# Analog_out.net
KiCad netlist of a schematic drawn in Altium Designer
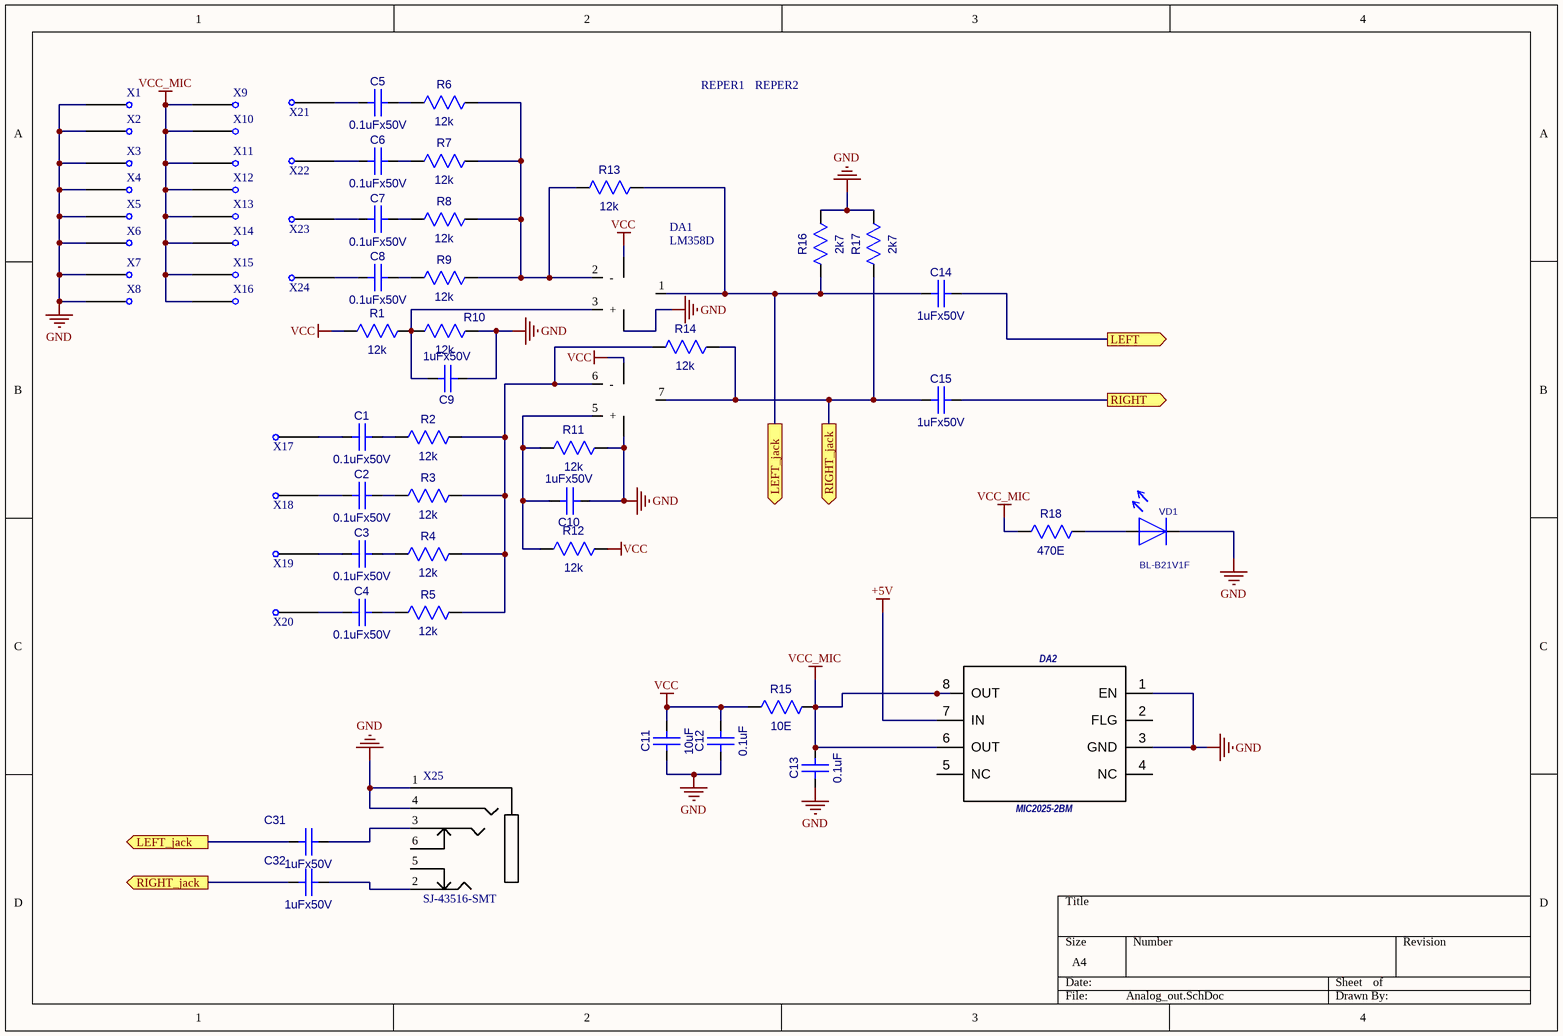
[diagram p0: Analog_out.SchDoc]

(export (version "E")
  (design (tool "Eeschema 10.0.6"))
  (components
    (comp (ref "C1")
      (value "0.1uFx50V")
      (footprint "CC0603-3M")
      (description "CC0603 X7R")
      (libsource (lib "gprs_modem") (part "CC0603"))
    )
    (comp (ref "C2")
      (value "0.1uFx50V")
      (footprint "CC0603-3M")
      (description "CC0603 X7R")
      (libsource (lib "gprs_modem") (part "CC0603"))
    )
    (comp (ref "C3")
      (value "0.1uFx50V")
      (footprint "CC0603-3M")
      (description "CC0603 X7R")
      (libsource (lib "gprs_modem") (part "CC0603"))
    )
    (comp (ref "C4")
      (value "0.1uFx50V")
      (footprint "CC0603-3M")
      (description "CC0603 X7R")
      (libsource (lib "gprs_modem") (part "CC0603"))
    )
    (comp (ref "C5")
      (value "0.1uFx50V")
      (footprint "CC0603-3M")
      (description "CC0603 X7R")
      (libsource (lib "gprs_modem") (part "CC0603"))
    )
    (comp (ref "C6")
      (value "0.1uFx50V")
      (footprint "CC0603-3M")
      (description "CC0603 X7R")
      (libsource (lib "gprs_modem") (part "CC0603"))
    )
    (comp (ref "C7")
      (value "0.1uFx50V")
      (footprint "CC0603-3M")
      (description "CC0603 X7R")
      (libsource (lib "gprs_modem") (part "CC0603"))
    )
    (comp (ref "C8")
      (value "0.1uFx50V")
      (footprint "CC0603-3M")
      (description "CC0603 X7R")
      (libsource (lib "gprs_modem") (part "CC0603"))
    )
    (comp (ref "C9")
      (value "1uFx50V")
      (footprint "CC0603-3M")
      (description "CC0603 X7R")
      (libsource (lib "gprs_modem") (part "CC0603"))
    )
    (comp (ref "C10")
      (value "1uFx50V")
      (footprint "CC0603-3M")
      (description "CC0603 X7R")
      (libsource (lib "gprs_modem") (part "CC0603"))
    )
    (comp (ref "C11")
      (value "10uF")
      (footprint "CC0805-MIDI-2M1")
      (description "CC0805")
      (libsource (lib "gprs_modem") (part "CC0805"))
    )
    (comp (ref "C12")
      (value "0.1uF")
      (footprint "CC0603-3M")
      (description "CC0603")
      (libsource (lib "gprs_modem") (part "CC0603"))
    )
    (comp (ref "C13")
      (value "0.1uF")
      (footprint "CC0603-3M")
      (description "CC0603")
      (libsource (lib "gprs_modem") (part "CC0603"))
    )
    (comp (ref "C14")
      (value "1uFx50V")
      (footprint "CC0603-3M")
      (description "CC0603 X7R")
      (libsource (lib "gprs_modem") (part "CC0603"))
    )
    (comp (ref "C15")
      (value "1uFx50V")
      (footprint "CC0603-3M")
      (description "CC0603 X7R")
      (libsource (lib "gprs_modem") (part "CC0603"))
    )
    (comp (ref "C31")
      (value "1uFx50V")
      (footprint "CC0603-3M")
      (description "CC0603 X7R")
      (libsource (lib "gprs_modem") (part "CC0603"))
    )
    (comp (ref "C32")
      (value "1uFx50V")
      (footprint "CC0603-3M")
      (description "CC0603 X7R")
      (libsource (lib "gprs_modem") (part "CC0603"))
    )
    (comp (ref "DA1") (value "LM358D") (footprint "SO-8") (libsource (lib "VHF") (part "LM358D")))
    (comp (ref "DA2") (value "MIC2025-2BM") (footprint "SO-8") (libsource (lib "*") (part "MIC2025-2BM")))
    (comp (ref "R1")
      (value "12k")
      (footprint "RC0603-3M")
      (description "RC0603")
      (libsource (lib "gprs_modem") (part "RC0603"))
    )
    (comp (ref "R2")
      (value "12k")
      (footprint "RC0603-3M")
      (description "RC0603")
      (libsource (lib "gprs_modem") (part "RC0603"))
    )
    (comp (ref "R3")
      (value "12k")
      (footprint "RC0603-3M")
      (description "RC0603")
      (libsource (lib "gprs_modem") (part "RC0603"))
    )
    (comp (ref "R4")
      (value "12k")
      (footprint "RC0603-3M")
      (description "RC0603")
      (libsource (lib "gprs_modem") (part "RC0603"))
    )
    (comp (ref "R5")
      (value "12k")
      (footprint "RC0603-3M")
      (description "RC0603")
      (libsource (lib "gprs_modem") (part "RC0603"))
    )
    (comp (ref "R6")
      (value "12k")
      (footprint "RC0603-3M")
      (description "RC0603")
      (libsource (lib "gprs_modem") (part "RC0603"))
    )
    (comp (ref "R7")
      (value "12k")
      (footprint "RC0603-3M")
      (description "RC0603")
      (libsource (lib "gprs_modem") (part "RC0603"))
    )
    (comp (ref "R8")
      (value "12k")
      (footprint "RC0603-3M")
      (description "RC0603")
      (libsource (lib "gprs_modem") (part "RC0603"))
    )
    (comp (ref "R9")
      (value "12k")
      (footprint "RC0603-3M")
      (description "RC0603")
      (libsource (lib "gprs_modem") (part "RC0603"))
    )
    (comp (ref "R10")
      (value "12k")
      (footprint "RC0603-3M")
      (description "RC0603")
      (libsource (lib "gprs_modem") (part "RC0603"))
    )
    (comp (ref "R11")
      (value "12k")
      (footprint "RC0603-3M")
      (description "RC0603")
      (libsource (lib "gprs_modem") (part "RC0603"))
    )
    (comp (ref "R12")
      (value "12k")
      (footprint "RC0603-3M")
      (description "RC0603")
      (libsource (lib "gprs_modem") (part "RC0603"))
    )
    (comp (ref "R13")
      (value "12k")
      (footprint "RC0603-3M")
      (description "RC0603")
      (libsource (lib "gprs_modem") (part "RC0603"))
    )
    (comp (ref "R14")
      (value "12k")
      (footprint "RC0603-3M")
      (description "RC0603")
      (libsource (lib "gprs_modem") (part "RC0603"))
    )
    (comp (ref "R15")
      (value "10E")
      (footprint "RC0805_IPC_NOM")
      (description "RC0805")
      (libsource (lib "gprs_modem") (part "RC0805"))
    )
    (comp (ref "R16")
      (value "2k7")
      (footprint "RC0603-3M")
      (description "RC0603")
      (libsource (lib "gprs_modem") (part "RC0603"))
    )
    (comp (ref "R17")
      (value "2k7")
      (footprint "RC0603-3M")
      (description "RC0603")
      (libsource (lib "gprs_modem") (part "RC0603"))
    )
    (comp (ref "R18")
      (value "470E")
      (footprint "RC0603-3M")
      (description "RC0603")
      (libsource (lib "gprs_modem") (part "RC0603"))
    )
    (comp (ref "REPER1")
      (value "REPER1.2")
      (footprint "REPER1.2")
      (libsource (lib "gprs_modem") (part "REPER1.2"))
    )
    (comp (ref "REPER2")
      (value "REPER1.2")
      (footprint "REPER1.2")
      (libsource (lib "gprs_modem") (part "REPER1.2"))
    )
    (comp (ref "VD1")
      (value "BL-B21V1F")
      (footprint "LED3")
      (description "LED_3")
      (libsource (lib "gprs_modem") (part "LED_3"))
    )
    (comp (ref "X1") (value "PIN_1mm") (footprint "PIN_1mm") (libsource (lib "gprs_modem") (part "PIN_1mm")))
    (comp (ref "X2") (value "PIN_1mm") (footprint "PIN_1mm") (libsource (lib "gprs_modem") (part "PIN_1mm")))
    (comp (ref "X3") (value "PIN_1mm") (footprint "PIN_1mm") (libsource (lib "gprs_modem") (part "PIN_1mm")))
    (comp (ref "X4") (value "PIN_1mm") (footprint "PIN_1mm") (libsource (lib "gprs_modem") (part "PIN_1mm")))
    (comp (ref "X5") (value "PIN_1mm") (footprint "PIN_1mm") (libsource (lib "gprs_modem") (part "PIN_1mm")))
    (comp (ref "X6") (value "PIN_1mm") (footprint "PIN_1mm") (libsource (lib "gprs_modem") (part "PIN_1mm")))
    (comp (ref "X7") (value "PIN_1mm") (footprint "PIN_1mm") (libsource (lib "gprs_modem") (part "PIN_1mm")))
    (comp (ref "X8") (value "PIN_1mm") (footprint "PIN_1mm") (libsource (lib "gprs_modem") (part "PIN_1mm")))
    (comp (ref "X9") (value "PIN_1mm") (footprint "PIN_1mm") (libsource (lib "gprs_modem") (part "PIN_1mm")))
    (comp (ref "X10") (value "PIN_1mm") (footprint "PIN_1mm") (libsource (lib "gprs_modem") (part "PIN_1mm")))
    (comp (ref "X11") (value "PIN_1mm") (footprint "PIN_1mm") (libsource (lib "gprs_modem") (part "PIN_1mm")))
    (comp (ref "X12") (value "PIN_1mm") (footprint "PIN_1mm") (libsource (lib "gprs_modem") (part "PIN_1mm")))
    (comp (ref "X13") (value "PIN_1mm") (footprint "PIN_1mm") (libsource (lib "gprs_modem") (part "PIN_1mm")))
    (comp (ref "X14") (value "PIN_1mm") (footprint "PIN_1mm") (libsource (lib "gprs_modem") (part "PIN_1mm")))
    (comp (ref "X15") (value "PIN_1mm") (footprint "PIN_1mm") (libsource (lib "gprs_modem") (part "PIN_1mm")))
    (comp (ref "X16") (value "PIN_1mm") (footprint "PIN_1mm") (libsource (lib "gprs_modem") (part "PIN_1mm")))
    (comp (ref "X17") (value "PIN_1mm") (footprint "PIN_1mm") (libsource (lib "gprs_modem") (part "PIN_1mm")))
    (comp (ref "X18") (value "PIN_1mm") (footprint "PIN_1mm") (libsource (lib "gprs_modem") (part "PIN_1mm")))
    (comp (ref "X19") (value "PIN_1mm") (footprint "PIN_1mm") (libsource (lib "gprs_modem") (part "PIN_1mm")))
    (comp (ref "X20") (value "PIN_1mm") (footprint "PIN_1mm") (libsource (lib "gprs_modem") (part "PIN_1mm")))
    (comp (ref "X21") (value "PIN_1mm") (footprint "PIN_1mm") (libsource (lib "gprs_modem") (part "PIN_1mm")))
    (comp (ref "X22") (value "PIN_1mm") (footprint "PIN_1mm") (libsource (lib "gprs_modem") (part "PIN_1mm")))
    (comp (ref "X23") (value "PIN_1mm") (footprint "PIN_1mm") (libsource (lib "gprs_modem") (part "PIN_1mm")))
    (comp (ref "X24") (value "PIN_1mm") (footprint "PIN_1mm") (libsource (lib "gprs_modem") (part "PIN_1mm")))
    (comp (ref "X25")
      (value "SJ-43516-SMT")
      (footprint "SJ-43516-SMT")
      (description "3.5mm connector 4 conductors")
      (libsource (lib "gprs_modem") (part "SJ-43516-SMT"))
    )
  )
  (nets
    (net (code "1") (name "+5V") (class "Default")
      (node (ref "DA2") (pin "7") (pinfunction "IN_7") (pintype "passive"))
    )
    (net (code "2") (name "/LEFT") (class "Default")
      (node (ref "C14") (pin "2") (pinfunction "B_2") (pintype "passive"))
    )
    (net (code "3") (name "/LEFT_jack") (class "Default")
      (node (ref "C14") (pin "1") (pinfunction "A_1") (pintype "passive"))
      (node (ref "C31") (pin "1") (pinfunction "A_1") (pintype "passive"))
      (node (ref "DA1") (pin "1") (pinfunction "Out1_1") (pintype "passive"))
      (node (ref "R13") (pin "2") (pinfunction "B_2") (pintype "passive"))
      (node (ref "R16") (pin "1") (pinfunction "A_1") (pintype "passive"))
    )
    (net (code "4") (name "/RIGHT") (class "Default")
      (node (ref "C15") (pin "2") (pinfunction "B_2") (pintype "passive"))
    )
    (net (code "5") (name "/RIGHT_jack") (class "Default")
      (node (ref "C15") (pin "1") (pinfunction "A_1") (pintype "passive"))
      (node (ref "C32") (pin "1") (pinfunction "A_1") (pintype "passive"))
      (node (ref "DA1") (pin "7") (pinfunction "Out2_7") (pintype "passive"))
      (node (ref "R14") (pin "2") (pinfunction "B_2") (pintype "passive"))
      (node (ref "R17") (pin "1") (pinfunction "A_1") (pintype "passive"))
    )
    (net (code "6") (name "GND") (class "Default")
      (node (ref "C10") (pin "1") (pinfunction "A_1") (pintype "passive"))
      (node (ref "C11") (pin "1") (pinfunction "A_1") (pintype "passive"))
      (node (ref "C12") (pin "1") (pinfunction "A_1") (pintype "passive"))
      (node (ref "C13") (pin "1") (pinfunction "A_1") (pintype "passive"))
      (node (ref "C9") (pin "1") (pinfunction "A_1") (pintype "passive"))
      (node (ref "DA1") (pin "4") (pinfunction "Vss_4") (pintype "passive"))
      (node (ref "DA2") (pin "1") (pinfunction "EN_1") (pintype "passive"))
      (node (ref "DA2") (pin "3") (pinfunction "GND_3") (pintype "passive"))
      (node (ref "R10") (pin "2") (pinfunction "B_2") (pintype "passive"))
      (node (ref "R11") (pin "2") (pinfunction "B_2") (pintype "passive"))
      (node (ref "R16") (pin "2") (pinfunction "B_2") (pintype "passive"))
      (node (ref "R17") (pin "2") (pinfunction "B_2") (pintype "passive"))
      (node (ref "VD1") (pin "1") (pintype "passive"))
      (node (ref "X1") (pin "1") (pinfunction "1_1") (pintype "passive"))
      (node (ref "X2") (pin "1") (pinfunction "1_1") (pintype "passive"))
      (node (ref "X25") (pin "1") (pinfunction "1_1") (pintype "passive"))
      (node (ref "X25") (pin "4") (pinfunction "4_4") (pintype "passive"))
      (node (ref "X3") (pin "1") (pinfunction "1_1") (pintype "passive"))
      (node (ref "X4") (pin "1") (pinfunction "1_1") (pintype "passive"))
      (node (ref "X5") (pin "1") (pinfunction "1_1") (pintype "passive"))
      (node (ref "X6") (pin "1") (pinfunction "1_1") (pintype "passive"))
      (node (ref "X7") (pin "1") (pinfunction "1_1") (pintype "passive"))
      (node (ref "X8") (pin "1") (pinfunction "1_1") (pintype "passive"))
    )
    (net (code "7") (name "Net-(C1-A)") (class "Default")
      (node (ref "C1") (pin "1") (pinfunction "A_1") (pintype "passive"))
      (node (ref "X17") (pin "1") (pinfunction "1_1") (pintype "passive"))
    )
    (net (code "8") (name "Net-(C1-B)") (class "Default")
      (node (ref "C1") (pin "2") (pinfunction "B_2") (pintype "passive"))
      (node (ref "R2") (pin "1") (pinfunction "A_1") (pintype "passive"))
    )
    (net (code "9") (name "Net-(C2-A)") (class "Default")
      (node (ref "C2") (pin "1") (pinfunction "A_1") (pintype "passive"))
      (node (ref "X18") (pin "1") (pinfunction "1_1") (pintype "passive"))
    )
    (net (code "10") (name "Net-(C2-B)") (class "Default")
      (node (ref "C2") (pin "2") (pinfunction "B_2") (pintype "passive"))
      (node (ref "R3") (pin "1") (pinfunction "A_1") (pintype "passive"))
    )
    (net (code "11") (name "Net-(C3-A)") (class "Default")
      (node (ref "C3") (pin "1") (pinfunction "A_1") (pintype "passive"))
      (node (ref "X19") (pin "1") (pinfunction "1_1") (pintype "passive"))
    )
    (net (code "12") (name "Net-(C3-B)") (class "Default")
      (node (ref "C3") (pin "2") (pinfunction "B_2") (pintype "passive"))
      (node (ref "R4") (pin "1") (pinfunction "A_1") (pintype "passive"))
    )
    (net (code "13") (name "Net-(C4-A)") (class "Default")
      (node (ref "C4") (pin "1") (pinfunction "A_1") (pintype "passive"))
      (node (ref "X20") (pin "1") (pinfunction "1_1") (pintype "passive"))
    )
    (net (code "14") (name "Net-(C4-B)") (class "Default")
      (node (ref "C4") (pin "2") (pinfunction "B_2") (pintype "passive"))
      (node (ref "R5") (pin "1") (pinfunction "A_1") (pintype "passive"))
    )
    (net (code "15") (name "Net-(C5-A)") (class "Default")
      (node (ref "C5") (pin "1") (pinfunction "A_1") (pintype "passive"))
      (node (ref "X21") (pin "1") (pinfunction "1_1") (pintype "passive"))
    )
    (net (code "16") (name "Net-(C5-B)") (class "Default")
      (node (ref "C5") (pin "2") (pinfunction "B_2") (pintype "passive"))
      (node (ref "R6") (pin "1") (pinfunction "A_1") (pintype "passive"))
    )
    (net (code "17") (name "Net-(C6-A)") (class "Default")
      (node (ref "C6") (pin "1") (pinfunction "A_1") (pintype "passive"))
      (node (ref "X22") (pin "1") (pinfunction "1_1") (pintype "passive"))
    )
    (net (code "18") (name "Net-(C6-B)") (class "Default")
      (node (ref "C6") (pin "2") (pinfunction "B_2") (pintype "passive"))
      (node (ref "R7") (pin "1") (pinfunction "A_1") (pintype "passive"))
    )
    (net (code "19") (name "Net-(C7-A)") (class "Default")
      (node (ref "C7") (pin "1") (pinfunction "A_1") (pintype "passive"))
      (node (ref "X23") (pin "1") (pinfunction "1_1") (pintype "passive"))
    )
    (net (code "20") (name "Net-(C7-B)") (class "Default")
      (node (ref "C7") (pin "2") (pinfunction "B_2") (pintype "passive"))
      (node (ref "R8") (pin "1") (pinfunction "A_1") (pintype "passive"))
    )
    (net (code "21") (name "Net-(C8-A)") (class "Default")
      (node (ref "C8") (pin "1") (pinfunction "A_1") (pintype "passive"))
      (node (ref "X24") (pin "1") (pinfunction "1_1") (pintype "passive"))
    )
    (net (code "22") (name "Net-(C8-B)") (class "Default")
      (node (ref "C8") (pin "2") (pinfunction "B_2") (pintype "passive"))
      (node (ref "R9") (pin "1") (pinfunction "A_1") (pintype "passive"))
    )
    (net (code "23") (name "Net-(C9-B)") (class "Default")
      (node (ref "C9") (pin "2") (pinfunction "B_2") (pintype "passive"))
      (node (ref "DA1") (pin "3") (pinfunction "+_3") (pintype "passive"))
      (node (ref "R1") (pin "2") (pinfunction "B_2") (pintype "passive"))
      (node (ref "R10") (pin "1") (pinfunction "A_1") (pintype "passive"))
    )
    (net (code "24") (name "Net-(C10-B)") (class "Default")
      (node (ref "C10") (pin "2") (pinfunction "B_2") (pintype "passive"))
      (node (ref "DA1") (pin "5") (pinfunction "+_5") (pintype "passive"))
      (node (ref "R11") (pin "1") (pinfunction "A_1") (pintype "passive"))
      (node (ref "R12") (pin "1") (pinfunction "A_1") (pintype "passive"))
    )
    (net (code "25") (name "Net-(C31-B)") (class "Default")
      (node (ref "C31") (pin "2") (pinfunction "B_2") (pintype "passive"))
      (node (ref "X25") (pin "3") (pinfunction "3_3") (pintype "passive"))
    )
    (net (code "26") (name "Net-(C32-B)") (class "Default")
      (node (ref "C32") (pin "2") (pinfunction "B_2") (pintype "passive"))
      (node (ref "X25") (pin "2") (pinfunction "2_2") (pintype "passive"))
    )
    (net (code "27") (name "Net-(R13-A)") (class "Default")
      (node (ref "DA1") (pin "2") (pinfunction "-_2") (pintype "passive"))
      (node (ref "R13") (pin "1") (pinfunction "A_1") (pintype "passive"))
      (node (ref "R6") (pin "2") (pinfunction "B_2") (pintype "passive"))
      (node (ref "R7") (pin "2") (pinfunction "B_2") (pintype "passive"))
      (node (ref "R8") (pin "2") (pinfunction "B_2") (pintype "passive"))
      (node (ref "R9") (pin "2") (pinfunction "B_2") (pintype "passive"))
    )
    (net (code "28") (name "Net-(R14-A)") (class "Default")
      (node (ref "DA1") (pin "6") (pinfunction "-_6") (pintype "passive"))
      (node (ref "R14") (pin "1") (pinfunction "A_1") (pintype "passive"))
      (node (ref "R2") (pin "2") (pinfunction "B_2") (pintype "passive"))
      (node (ref "R3") (pin "2") (pinfunction "B_2") (pintype "passive"))
      (node (ref "R4") (pin "2") (pinfunction "B_2") (pintype "passive"))
      (node (ref "R5") (pin "2") (pinfunction "B_2") (pintype "passive"))
    )
    (net (code "29") (name "Net-(R18-B)") (class "Default")
      (node (ref "R18") (pin "2") (pinfunction "B_2") (pintype "passive"))
      (node (ref "VD1") (pin "2") (pintype "passive"))
    )
    (net (code "30") (name "VCC") (class "Default")
      (node (ref "C11") (pin "2") (pinfunction "B_2") (pintype "passive"))
      (node (ref "C12") (pin "2") (pinfunction "B_2") (pintype "passive"))
      (node (ref "DA1") (pin "8") (pinfunction "Vdd_8") (pintype "passive"))
      (node (ref "R1") (pin "1") (pinfunction "A_1") (pintype "passive"))
      (node (ref "R12") (pin "2") (pinfunction "B_2") (pintype "passive"))
      (node (ref "R15") (pin "1") (pinfunction "A_1") (pintype "passive"))
    )
    (net (code "31") (name "VCC_MIC") (class "Default")
      (node (ref "C13") (pin "2") (pinfunction "B_2") (pintype "passive"))
      (node (ref "DA2") (pin "6") (pinfunction "OUT_6") (pintype "passive"))
      (node (ref "DA2") (pin "8") (pinfunction "OUT_8") (pintype "passive"))
      (node (ref "R15") (pin "2") (pinfunction "B_2") (pintype "passive"))
      (node (ref "R18") (pin "1") (pinfunction "A_1") (pintype "passive"))
      (node (ref "X10") (pin "1") (pinfunction "1_1") (pintype "passive"))
      (node (ref "X11") (pin "1") (pinfunction "1_1") (pintype "passive"))
      (node (ref "X12") (pin "1") (pinfunction "1_1") (pintype "passive"))
      (node (ref "X13") (pin "1") (pinfunction "1_1") (pintype "passive"))
      (node (ref "X14") (pin "1") (pinfunction "1_1") (pintype "passive"))
      (node (ref "X15") (pin "1") (pinfunction "1_1") (pintype "passive"))
      (node (ref "X16") (pin "1") (pinfunction "1_1") (pintype "passive"))
      (node (ref "X9") (pin "1") (pinfunction "1_1") (pintype "passive"))
    )
    (net (code "32") (name "unconnected-(DA2-FLG-Pad2)") (class "Default")
      (node (ref "DA2") (pin "2") (pinfunction "FLG_2") (pintype "passive"))
    )
    (net (code "33") (name "unconnected-(DA2-NC-Pad4)") (class "Default")
      (node (ref "DA2") (pin "4") (pinfunction "NC_4") (pintype "passive"))
    )
    (net (code "34") (name "unconnected-(DA2-NC-Pad5)") (class "Default")
      (node (ref "DA2") (pin "5") (pinfunction "NC_5") (pintype "passive"))
    )
    (net (code "35") (name "unconnected-(REPER1-Pad1)") (class "Default")
      (node (ref "REPER1") (pin "1") (pintype "passive"))
    )
    (net (code "36") (name "unconnected-(REPER2-Pad1)") (class "Default")
      (node (ref "REPER2") (pin "1") (pintype "passive"))
    )
    (net (code "37") (name "unconnected-(X25-Pad5)") (class "Default")
      (node (ref "X25") (pin "5") (pinfunction "5_5") (pintype "passive"))
    )
    (net (code "38") (name "unconnected-(X25-Pad6)") (class "Default")
      (node (ref "X25") (pin "6") (pinfunction "6_6") (pintype "passive"))
    )
  )
)
